# phase_and_amplifier.net
KiCad netlist of a schematic drawn in EAGLE
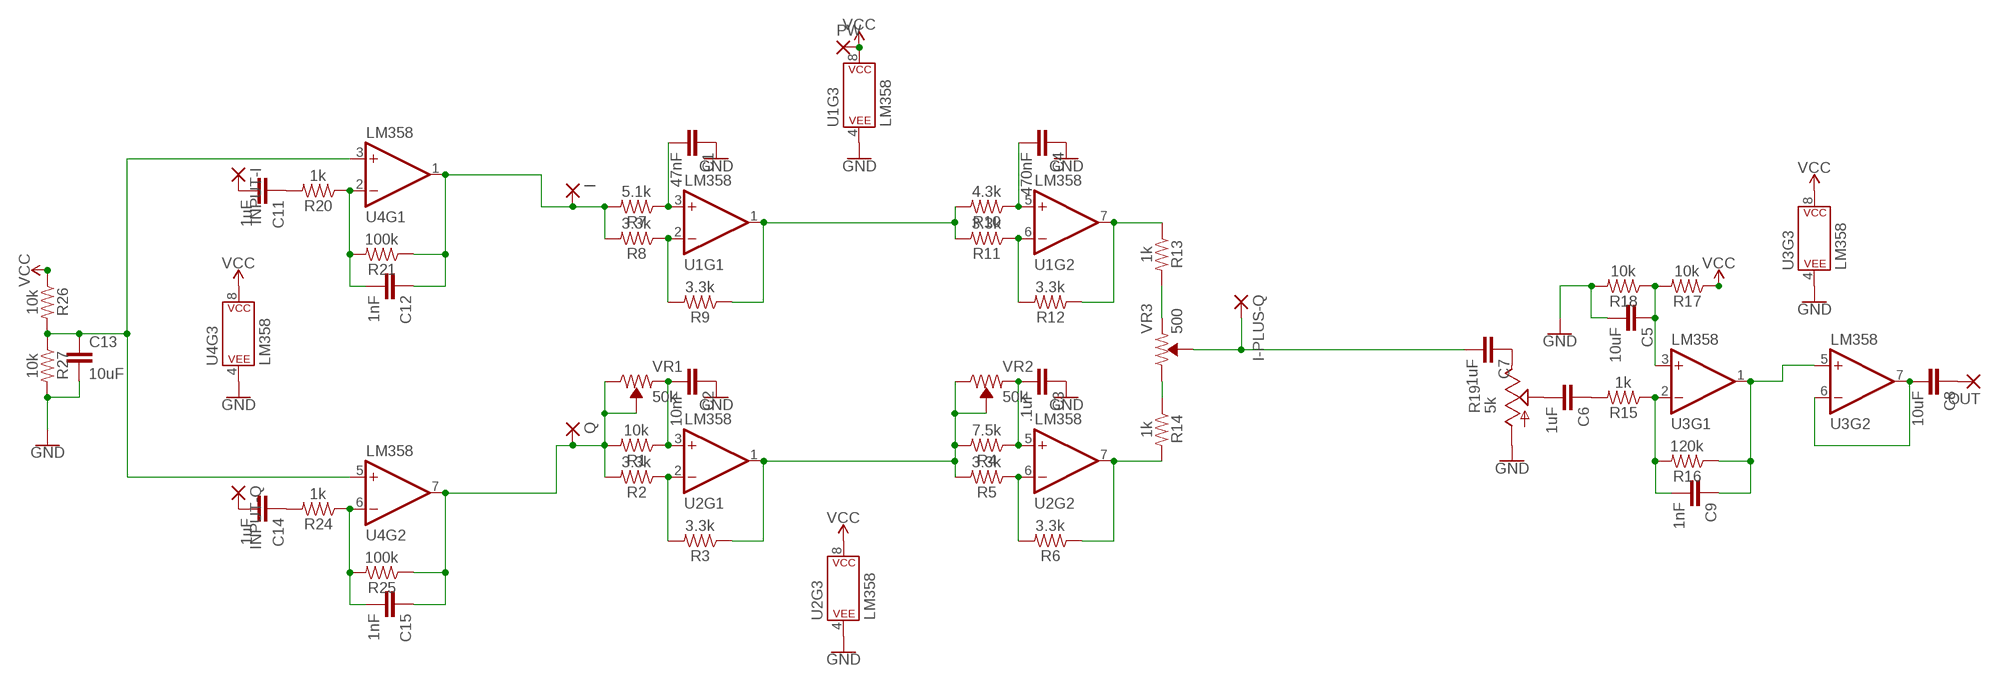
[diagram p0: schematic, sheet 1]

(export (version "E")
  (design (tool "Eeschema 10.0.6"))
  (components
    (comp (ref "C1")
      (value "47nF")
      (footprint "eagle-import:C5B3.5")
      (libsource (lib "eagle-import") (part "C5/3.5"))
    )
    (comp (ref "C2")
      (value "10nF")
      (footprint "eagle-import:C5B3.5")
      (libsource (lib "eagle-import") (part "C5/3.5"))
    )
    (comp (ref "C3")
      (value ".1uF")
      (footprint "eagle-import:C5B3.5")
      (libsource (lib "eagle-import") (part "C5/3.5"))
    )
    (comp (ref "C4")
      (value "470nF")
      (footprint "eagle-import:C5B3.5")
      (libsource (lib "eagle-import") (part "C5/3.5"))
    )
    (comp (ref "C5")
      (value "10uF")
      (footprint "eagle-import:C5B3.5")
      (libsource (lib "eagle-import") (part "C5/3.5"))
    )
    (comp (ref "C6")
      (value "1uF")
      (footprint "eagle-import:C5B3.5")
      (libsource (lib "eagle-import") (part "C5/3.5"))
    )
    (comp (ref "C7")
      (value "1uF")
      (footprint "eagle-import:C5B3.5")
      (libsource (lib "eagle-import") (part "C5/3.5"))
    )
    (comp (ref "C8")
      (value "10uF")
      (footprint "eagle-import:C5B3.5")
      (libsource (lib "eagle-import") (part "C5/3.5"))
    )
    (comp (ref "C9")
      (value "1nF")
      (footprint "eagle-import:C5B3.5")
      (libsource (lib "eagle-import") (part "C5/3.5"))
    )
    (comp (ref "C11")
      (value "1uF")
      (footprint "eagle-import:C5B3.5")
      (libsource (lib "eagle-import") (part "C5/3.5"))
    )
    (comp (ref "C12")
      (value "1nF")
      (footprint "eagle-import:C5B3.5")
      (libsource (lib "eagle-import") (part "C5/3.5"))
    )
    (comp (ref "C13")
      (value "10uF")
      (footprint "eagle-import:C5B3.5")
      (libsource (lib "eagle-import") (part "C5/3.5"))
    )
    (comp (ref "C14")
      (value "1uF")
      (footprint "eagle-import:C5B3.5")
      (libsource (lib "eagle-import") (part "C5/3.5"))
    )
    (comp (ref "C15")
      (value "1nF")
      (footprint "eagle-import:C5B3.5")
      (libsource (lib "eagle-import") (part "C5/3.5"))
    )
    (comp (ref "I")
      (value "2,54/1,1")
      (footprint "eagle-import:2,54_1,1")
      (libsource (lib "eagle-import") (part "2,54/1,1"))
    )
    (comp (ref "I-PLUS-Q")
      (value "2,54/1,1")
      (footprint "eagle-import:2,54_1,1")
      (libsource (lib "eagle-import") (part "2,54/1,1"))
    )
    (comp (ref "INPUT-I")
      (value "2,54/1,1")
      (footprint "eagle-import:2,54_1,1")
      (libsource (lib "eagle-import") (part "2,54/1,1"))
    )
    (comp (ref "INPUT-Q")
      (value "2,54/1,1")
      (footprint "eagle-import:2,54_1,1")
      (libsource (lib "eagle-import") (part "2,54/1,1"))
    )
    (comp (ref "OUT")
      (value "2,54/1,1")
      (footprint "eagle-import:2,54_1,1")
      (libsource (lib "eagle-import") (part "2,54/1,1"))
    )
    (comp (ref "PW")
      (value "2,54/1,1")
      (footprint "eagle-import:2,54_1,1")
      (libsource (lib "eagle-import") (part "2,54/1,1"))
    )
    (comp (ref "Q")
      (value "2,54/1,1")
      (footprint "eagle-import:2,54_1,1")
      (libsource (lib "eagle-import") (part "2,54/1,1"))
    )
    (comp (ref "R1")
      (value "10k")
      (footprint "eagle-import:AXIAL-0.3")
      (libsource (lib "eagle-import") (part "1KOHM-HORIZ-1/4W-1%"))
    )
    (comp (ref "R2")
      (value "3.3k")
      (footprint "eagle-import:AXIAL-0.3")
      (libsource (lib "eagle-import") (part "1KOHM-HORIZ-1/4W-1%"))
    )
    (comp (ref "R3")
      (value "3.3k")
      (footprint "eagle-import:AXIAL-0.3")
      (libsource (lib "eagle-import") (part "1KOHM-HORIZ-1/4W-1%"))
    )
    (comp (ref "R4")
      (value "7.5k")
      (footprint "eagle-import:AXIAL-0.3")
      (libsource (lib "eagle-import") (part "1KOHM-HORIZ-1/4W-1%"))
    )
    (comp (ref "R5")
      (value "3.3k")
      (footprint "eagle-import:AXIAL-0.3")
      (libsource (lib "eagle-import") (part "1KOHM-HORIZ-1/4W-1%"))
    )
    (comp (ref "R6")
      (value "3.3k")
      (footprint "eagle-import:AXIAL-0.3")
      (libsource (lib "eagle-import") (part "1KOHM-HORIZ-1/4W-1%"))
    )
    (comp (ref "R7")
      (value "5.1k")
      (footprint "eagle-import:AXIAL-0.3")
      (libsource (lib "eagle-import") (part "1KOHM-HORIZ-1/4W-1%"))
    )
    (comp (ref "R8")
      (value "3.3k")
      (footprint "eagle-import:AXIAL-0.3")
      (libsource (lib "eagle-import") (part "1KOHM-HORIZ-1/4W-1%"))
    )
    (comp (ref "R9")
      (value "3.3k")
      (footprint "eagle-import:AXIAL-0.3")
      (libsource (lib "eagle-import") (part "1KOHM-HORIZ-1/4W-1%"))
    )
    (comp (ref "R10")
      (value "4.3k")
      (footprint "eagle-import:AXIAL-0.3")
      (libsource (lib "eagle-import") (part "1KOHM-HORIZ-1/4W-1%"))
    )
    (comp (ref "R11")
      (value "3.3k")
      (footprint "eagle-import:AXIAL-0.3")
      (libsource (lib "eagle-import") (part "1KOHM-HORIZ-1/4W-1%"))
    )
    (comp (ref "R12")
      (value "3.3k")
      (footprint "eagle-import:AXIAL-0.3")
      (libsource (lib "eagle-import") (part "1KOHM-HORIZ-1/4W-1%"))
    )
    (comp (ref "R13")
      (value "1k")
      (footprint "eagle-import:AXIAL-0.3")
      (libsource (lib "eagle-import") (part "1KOHM-HORIZ-1/4W-1%"))
    )
    (comp (ref "R14")
      (value "1k")
      (footprint "eagle-import:AXIAL-0.3")
      (libsource (lib "eagle-import") (part "1KOHM-HORIZ-1/4W-1%"))
    )
    (comp (ref "R15")
      (value "1k")
      (footprint "eagle-import:AXIAL-0.3")
      (libsource (lib "eagle-import") (part "1KOHM-HORIZ-1/4W-1%"))
    )
    (comp (ref "R16")
      (value "120k")
      (footprint "eagle-import:AXIAL-0.3")
      (libsource (lib "eagle-import") (part "1KOHM-HORIZ-1/4W-1%"))
    )
    (comp (ref "R17")
      (value "10k")
      (footprint "eagle-import:AXIAL-0.3")
      (libsource (lib "eagle-import") (part "1KOHM-HORIZ-1/4W-1%"))
    )
    (comp (ref "R18")
      (value "10k")
      (footprint "eagle-import:AXIAL-0.3")
      (libsource (lib "eagle-import") (part "1KOHM-HORIZ-1/4W-1%"))
    )
    (comp (ref "R19")
      (value "5k")
      (footprint "eagle-import:B25V")
      (libsource (lib "eagle-import") (part "TRIM_US-B25V"))
    )
    (comp (ref "R20")
      (value "1k")
      (footprint "eagle-import:AXIAL-0.3")
      (libsource (lib "eagle-import") (part "1KOHM-HORIZ-1/4W-1%"))
    )
    (comp (ref "R21")
      (value "100k")
      (footprint "eagle-import:AXIAL-0.3")
      (libsource (lib "eagle-import") (part "1KOHM-HORIZ-1/4W-1%"))
    )
    (comp (ref "R24")
      (value "1k")
      (footprint "eagle-import:AXIAL-0.3")
      (libsource (lib "eagle-import") (part "1KOHM-HORIZ-1/4W-1%"))
    )
    (comp (ref "R25")
      (value "100k")
      (footprint "eagle-import:AXIAL-0.3")
      (libsource (lib "eagle-import") (part "1KOHM-HORIZ-1/4W-1%"))
    )
    (comp (ref "R26")
      (value "10k")
      (footprint "eagle-import:AXIAL-0.3")
      (libsource (lib "eagle-import") (part "1KOHM-HORIZ-1/4W-1%"))
    )
    (comp (ref "R27")
      (value "10k")
      (footprint "eagle-import:AXIAL-0.3")
      (libsource (lib "eagle-import") (part "1KOHM-HORIZ-1/4W-1%"))
    )
    (comp (ref "U1")
      (value "LM358")
      (footprint "eagle-import:DIP08")
      (libsource (lib "eagle-import") (part "LM358"))
    )
    (comp (ref "U2")
      (value "LM358")
      (footprint "eagle-import:DIP08")
      (libsource (lib "eagle-import") (part "LM358"))
    )
    (comp (ref "U3")
      (value "LM358")
      (footprint "eagle-import:DIP08")
      (libsource (lib "eagle-import") (part "LM358"))
    )
    (comp (ref "U4")
      (value "LM358")
      (footprint "eagle-import:DIP08")
      (libsource (lib "eagle-import") (part "LM358"))
    )
    (comp (ref "VR1")
      (value "50k")
      (footprint "eagle-import:TRIMPOT-PTH-3386U")
      (libsource (lib "eagle-import") (part "TRIMPOT-PTH-10MM-KNOB-1/2W-10%"))
    )
    (comp (ref "VR2")
      (value "50k")
      (footprint "eagle-import:TRIMPOT-PTH-3386U")
      (libsource (lib "eagle-import") (part "TRIMPOT-PTH-10MM-KNOB-1/2W-10%"))
    )
    (comp (ref "VR3")
      (value "500")
      (footprint "eagle-import:TRIMPOT-PTH-3386U")
      (libsource (lib "eagle-import") (part "TRIMPOT-PTH-10MM-KNOB-1/2W-10%"))
    )
  )
  (nets
    (net (code "1") (name "GND") (class "Default")
      (node (ref "C1") (pin "1") (pinfunction "1_1") (pintype "passive"))
      (node (ref "C13") (pin "2") (pinfunction "2_2") (pintype "passive"))
      (node (ref "C2") (pin "1") (pinfunction "1_1") (pintype "passive"))
      (node (ref "C3") (pin "1") (pinfunction "1_1") (pintype "passive"))
      (node (ref "C4") (pin "1") (pinfunction "1_1") (pintype "passive"))
      (node (ref "C5") (pin "2") (pinfunction "2_2") (pintype "passive"))
      (node (ref "R18") (pin "P$2") (pinfunction "2_P$2") (pintype "passive"))
      (node (ref "R19") (pin "A") (pinfunction "A_A") (pintype "passive"))
      (node (ref "R27") (pin "P$2") (pinfunction "2_P$2") (pintype "passive"))
      (node (ref "U1") (pin "4") (pinfunction "P$V-_4") (pintype "bidirectional"))
      (node (ref "U2") (pin "4") (pinfunction "P$V-_4") (pintype "bidirectional"))
      (node (ref "U3") (pin "4") (pinfunction "P$V-_4") (pintype "bidirectional"))
      (node (ref "U4") (pin "4") (pinfunction "P$V-_4") (pintype "bidirectional"))
    )
    (net (code "2") (name "Net-(C6-Pad2)") (class "Default")
      (node (ref "C6") (pin "2") (pinfunction "2_2") (pintype "passive"))
      (node (ref "R19") (pin "S") (pinfunction "S_S") (pintype "passive"))
    )
    (net (code "3") (name "Net-(C7-Pad1)") (class "Default")
      (node (ref "C7") (pin "1") (pinfunction "1_1") (pintype "passive"))
      (node (ref "R19") (pin "E") (pinfunction "E_E") (pintype "passive"))
    )
    (net (code "4") (name "Net-(I-P)") (class "Default")
      (node (ref "C12") (pin "1") (pinfunction "1_1") (pintype "passive"))
      (node (ref "I") (pin "1") (pinfunction "P_1") (pintype "passive"))
      (node (ref "R21") (pin "P$1") (pinfunction "1_P$1") (pintype "passive"))
      (node (ref "R7") (pin "P$2") (pinfunction "2_P$2") (pintype "passive"))
      (node (ref "R8") (pin "P$2") (pinfunction "2_P$2") (pintype "passive"))
      (node (ref "U4") (pin "1") (pinfunction "OUT_1") (pintype "output"))
    )
    (net (code "5") (name "Net-(I-PLUS-Q-P)") (class "Default")
      (node (ref "C7") (pin "2") (pinfunction "2_2") (pintype "passive"))
      (node (ref "I-PLUS-Q") (pin "1") (pinfunction "P_1") (pintype "passive"))
      (node (ref "VR3") (pin "2") (pinfunction "WIPER_2") (pintype "passive"))
    )
    (net (code "6") (name "Net-(INPUT-I-P)") (class "Default")
      (node (ref "C11") (pin "2") (pinfunction "2_2") (pintype "passive"))
      (node (ref "INPUT-I") (pin "1") (pinfunction "P_1") (pintype "passive"))
    )
    (net (code "7") (name "Net-(INPUT-Q-P)") (class "Default")
      (node (ref "C14") (pin "2") (pinfunction "2_2") (pintype "passive"))
      (node (ref "INPUT-Q") (pin "1") (pinfunction "P_1") (pintype "passive"))
    )
    (net (code "8") (name "Net-(OUT-P)") (class "Default")
      (node (ref "C8") (pin "1") (pinfunction "1_1") (pintype "passive"))
      (node (ref "OUT") (pin "1") (pinfunction "P_1") (pintype "passive"))
    )
    (net (code "9") (name "Net-(Q-P)") (class "Default")
      (node (ref "C15") (pin "1") (pinfunction "1_1") (pintype "passive"))
      (node (ref "Q") (pin "1") (pinfunction "P_1") (pintype "passive"))
      (node (ref "R1") (pin "P$2") (pinfunction "2_P$2") (pintype "passive"))
      (node (ref "R2") (pin "P$2") (pinfunction "2_P$2") (pintype "passive"))
      (node (ref "R25") (pin "P$1") (pinfunction "1_P$1") (pintype "passive"))
      (node (ref "U4") (pin "7") (pinfunction "OUT_7") (pintype "output"))
      (node (ref "VR1") (pin "2") (pinfunction "WIPER_2") (pintype "passive"))
      (node (ref "VR1") (pin "3") (pinfunction "CW_3") (pintype "passive"))
    )
    (net (code "10") (name "Net-(R1-1)") (class "Default")
      (node (ref "C2") (pin "2") (pinfunction "2_2") (pintype "passive"))
      (node (ref "R1") (pin "P$1") (pinfunction "1_P$1") (pintype "passive"))
      (node (ref "U2") (pin "3") (pinfunction "+IN_3") (pintype "input"))
      (node (ref "VR1") (pin "1") (pinfunction "CCW_1") (pintype "passive"))
    )
    (net (code "11") (name "Net-(R2-1)") (class "Default")
      (node (ref "R2") (pin "P$1") (pinfunction "1_P$1") (pintype "passive"))
      (node (ref "R3") (pin "P$2") (pinfunction "2_P$2") (pintype "passive"))
      (node (ref "U2") (pin "2") (pinfunction "-IN_2") (pintype "input"))
    )
    (net (code "12") (name "Net-(R3-1)") (class "Default")
      (node (ref "R3") (pin "P$1") (pinfunction "1_P$1") (pintype "passive"))
      (node (ref "R4") (pin "P$2") (pinfunction "2_P$2") (pintype "passive"))
      (node (ref "R5") (pin "P$2") (pinfunction "2_P$2") (pintype "passive"))
      (node (ref "U2") (pin "1") (pinfunction "OUT_1") (pintype "output"))
      (node (ref "VR2") (pin "2") (pinfunction "WIPER_2") (pintype "passive"))
      (node (ref "VR2") (pin "3") (pinfunction "CW_3") (pintype "passive"))
    )
    (net (code "13") (name "Net-(R4-1)") (class "Default")
      (node (ref "C3") (pin "2") (pinfunction "2_2") (pintype "passive"))
      (node (ref "R4") (pin "P$1") (pinfunction "1_P$1") (pintype "passive"))
      (node (ref "U2") (pin "5") (pinfunction "+IN_5") (pintype "input"))
      (node (ref "VR2") (pin "1") (pinfunction "CCW_1") (pintype "passive"))
    )
    (net (code "14") (name "Net-(R5-1)") (class "Default")
      (node (ref "R5") (pin "P$1") (pinfunction "1_P$1") (pintype "passive"))
      (node (ref "R6") (pin "P$2") (pinfunction "2_P$2") (pintype "passive"))
      (node (ref "U2") (pin "6") (pinfunction "-IN_6") (pintype "input"))
    )
    (net (code "15") (name "Net-(R7-1)") (class "Default")
      (node (ref "C1") (pin "2") (pinfunction "2_2") (pintype "passive"))
      (node (ref "R7") (pin "P$1") (pinfunction "1_P$1") (pintype "passive"))
      (node (ref "U1") (pin "3") (pinfunction "+IN_3") (pintype "input"))
    )
    (net (code "16") (name "Net-(R8-1)") (class "Default")
      (node (ref "R8") (pin "P$1") (pinfunction "1_P$1") (pintype "passive"))
      (node (ref "R9") (pin "P$2") (pinfunction "2_P$2") (pintype "passive"))
      (node (ref "U1") (pin "2") (pinfunction "-IN_2") (pintype "input"))
    )
    (net (code "17") (name "Net-(R10-1)") (class "Default")
      (node (ref "C4") (pin "2") (pinfunction "2_2") (pintype "passive"))
      (node (ref "R10") (pin "P$1") (pinfunction "1_P$1") (pintype "passive"))
      (node (ref "U1") (pin "5") (pinfunction "+IN_5") (pintype "input"))
    )
    (net (code "18") (name "Net-(R10-2)") (class "Default")
      (node (ref "R10") (pin "P$2") (pinfunction "2_P$2") (pintype "passive"))
      (node (ref "R11") (pin "P$2") (pinfunction "2_P$2") (pintype "passive"))
      (node (ref "R9") (pin "P$1") (pinfunction "1_P$1") (pintype "passive"))
      (node (ref "U1") (pin "1") (pinfunction "OUT_1") (pintype "output"))
    )
    (net (code "19") (name "Net-(R11-1)") (class "Default")
      (node (ref "R11") (pin "P$1") (pinfunction "1_P$1") (pintype "passive"))
      (node (ref "R12") (pin "P$2") (pinfunction "2_P$2") (pintype "passive"))
      (node (ref "U1") (pin "6") (pinfunction "-IN_6") (pintype "input"))
    )
    (net (code "20") (name "Net-(R12-1)") (class "Default")
      (node (ref "R12") (pin "P$1") (pinfunction "1_P$1") (pintype "passive"))
      (node (ref "R13") (pin "P$1") (pinfunction "1_P$1") (pintype "passive"))
      (node (ref "U1") (pin "7") (pinfunction "OUT_7") (pintype "output"))
    )
    (net (code "21") (name "Net-(R13-2)") (class "Default")
      (node (ref "R13") (pin "P$2") (pinfunction "2_P$2") (pintype "passive"))
      (node (ref "VR3") (pin "1") (pinfunction "CCW_1") (pintype "passive"))
    )
    (net (code "22") (name "Net-(R14-1)") (class "Default")
      (node (ref "R14") (pin "P$1") (pinfunction "1_P$1") (pintype "passive"))
      (node (ref "VR3") (pin "3") (pinfunction "CW_3") (pintype "passive"))
    )
    (net (code "23") (name "Net-(R14-2)") (class "Default")
      (node (ref "R14") (pin "P$2") (pinfunction "2_P$2") (pintype "passive"))
      (node (ref "R6") (pin "P$1") (pinfunction "1_P$1") (pintype "passive"))
      (node (ref "U2") (pin "7") (pinfunction "OUT_7") (pintype "output"))
    )
    (net (code "24") (name "Net-(R15-1)") (class "Default")
      (node (ref "C9") (pin "2") (pinfunction "2_2") (pintype "passive"))
      (node (ref "R15") (pin "P$1") (pinfunction "1_P$1") (pintype "passive"))
      (node (ref "R16") (pin "P$2") (pinfunction "2_P$2") (pintype "passive"))
      (node (ref "U3") (pin "2") (pinfunction "-IN_2") (pintype "input"))
    )
    (net (code "25") (name "Net-(R15-2)") (class "Default")
      (node (ref "C6") (pin "1") (pinfunction "1_1") (pintype "passive"))
      (node (ref "R15") (pin "P$2") (pinfunction "2_P$2") (pintype "passive"))
    )
    (net (code "26") (name "Net-(R16-1)") (class "Default")
      (node (ref "C9") (pin "1") (pinfunction "1_1") (pintype "passive"))
      (node (ref "R16") (pin "P$1") (pinfunction "1_P$1") (pintype "passive"))
      (node (ref "U3") (pin "1") (pinfunction "OUT_1") (pintype "output"))
      (node (ref "U3") (pin "5") (pinfunction "+IN_5") (pintype "input"))
    )
    (net (code "27") (name "Net-(R17-2)") (class "Default")
      (node (ref "C5") (pin "1") (pinfunction "1_1") (pintype "passive"))
      (node (ref "R17") (pin "P$2") (pinfunction "2_P$2") (pintype "passive"))
      (node (ref "R18") (pin "P$1") (pinfunction "1_P$1") (pintype "passive"))
      (node (ref "U3") (pin "3") (pinfunction "+IN_3") (pintype "input"))
    )
    (net (code "28") (name "Net-(R20-1)") (class "Default")
      (node (ref "C12") (pin "2") (pinfunction "2_2") (pintype "passive"))
      (node (ref "R20") (pin "P$1") (pinfunction "1_P$1") (pintype "passive"))
      (node (ref "R21") (pin "P$2") (pinfunction "2_P$2") (pintype "passive"))
      (node (ref "U4") (pin "2") (pinfunction "-IN_2") (pintype "input"))
    )
    (net (code "29") (name "Net-(R20-2)") (class "Default")
      (node (ref "C11") (pin "1") (pinfunction "1_1") (pintype "passive"))
      (node (ref "R20") (pin "P$2") (pinfunction "2_P$2") (pintype "passive"))
    )
    (net (code "30") (name "Net-(R24-1)") (class "Default")
      (node (ref "C15") (pin "2") (pinfunction "2_2") (pintype "passive"))
      (node (ref "R24") (pin "P$1") (pinfunction "1_P$1") (pintype "passive"))
      (node (ref "R25") (pin "P$2") (pinfunction "2_P$2") (pintype "passive"))
      (node (ref "U4") (pin "6") (pinfunction "-IN_6") (pintype "input"))
    )
    (net (code "31") (name "Net-(R24-2)") (class "Default")
      (node (ref "C14") (pin "1") (pinfunction "1_1") (pintype "passive"))
      (node (ref "R24") (pin "P$2") (pinfunction "2_P$2") (pintype "passive"))
    )
    (net (code "32") (name "Net-(R26-2)") (class "Default")
      (node (ref "C13") (pin "1") (pinfunction "1_1") (pintype "passive"))
      (node (ref "R26") (pin "P$2") (pinfunction "2_P$2") (pintype "passive"))
      (node (ref "R27") (pin "P$1") (pinfunction "1_P$1") (pintype "passive"))
      (node (ref "U4") (pin "3") (pinfunction "+IN_3") (pintype "input"))
      (node (ref "U4") (pin "5") (pinfunction "+IN_5") (pintype "input"))
    )
    (net (code "33") (name "Net-(U3B--IN)") (class "Default")
      (node (ref "C8") (pin "2") (pinfunction "2_2") (pintype "passive"))
      (node (ref "U3") (pin "6") (pinfunction "-IN_6") (pintype "input"))
      (node (ref "U3") (pin "7") (pinfunction "OUT_7") (pintype "output"))
    )
    (net (code "34") (name "VCC") (class "Default")
      (node (ref "PW") (pin "1") (pinfunction "P_1") (pintype "passive"))
      (node (ref "R17") (pin "P$1") (pinfunction "1_P$1") (pintype "passive"))
      (node (ref "R26") (pin "P$1") (pinfunction "1_P$1") (pintype "passive"))
      (node (ref "U1") (pin "8") (pinfunction "P$V+_8") (pintype "bidirectional"))
      (node (ref "U2") (pin "8") (pinfunction "P$V+_8") (pintype "bidirectional"))
      (node (ref "U3") (pin "8") (pinfunction "P$V+_8") (pintype "bidirectional"))
      (node (ref "U4") (pin "8") (pinfunction "P$V+_8") (pintype "bidirectional"))
    )
  )
)
